# sch_CPU.net
KiCad netlist of a schematic drawn in Altium Designer
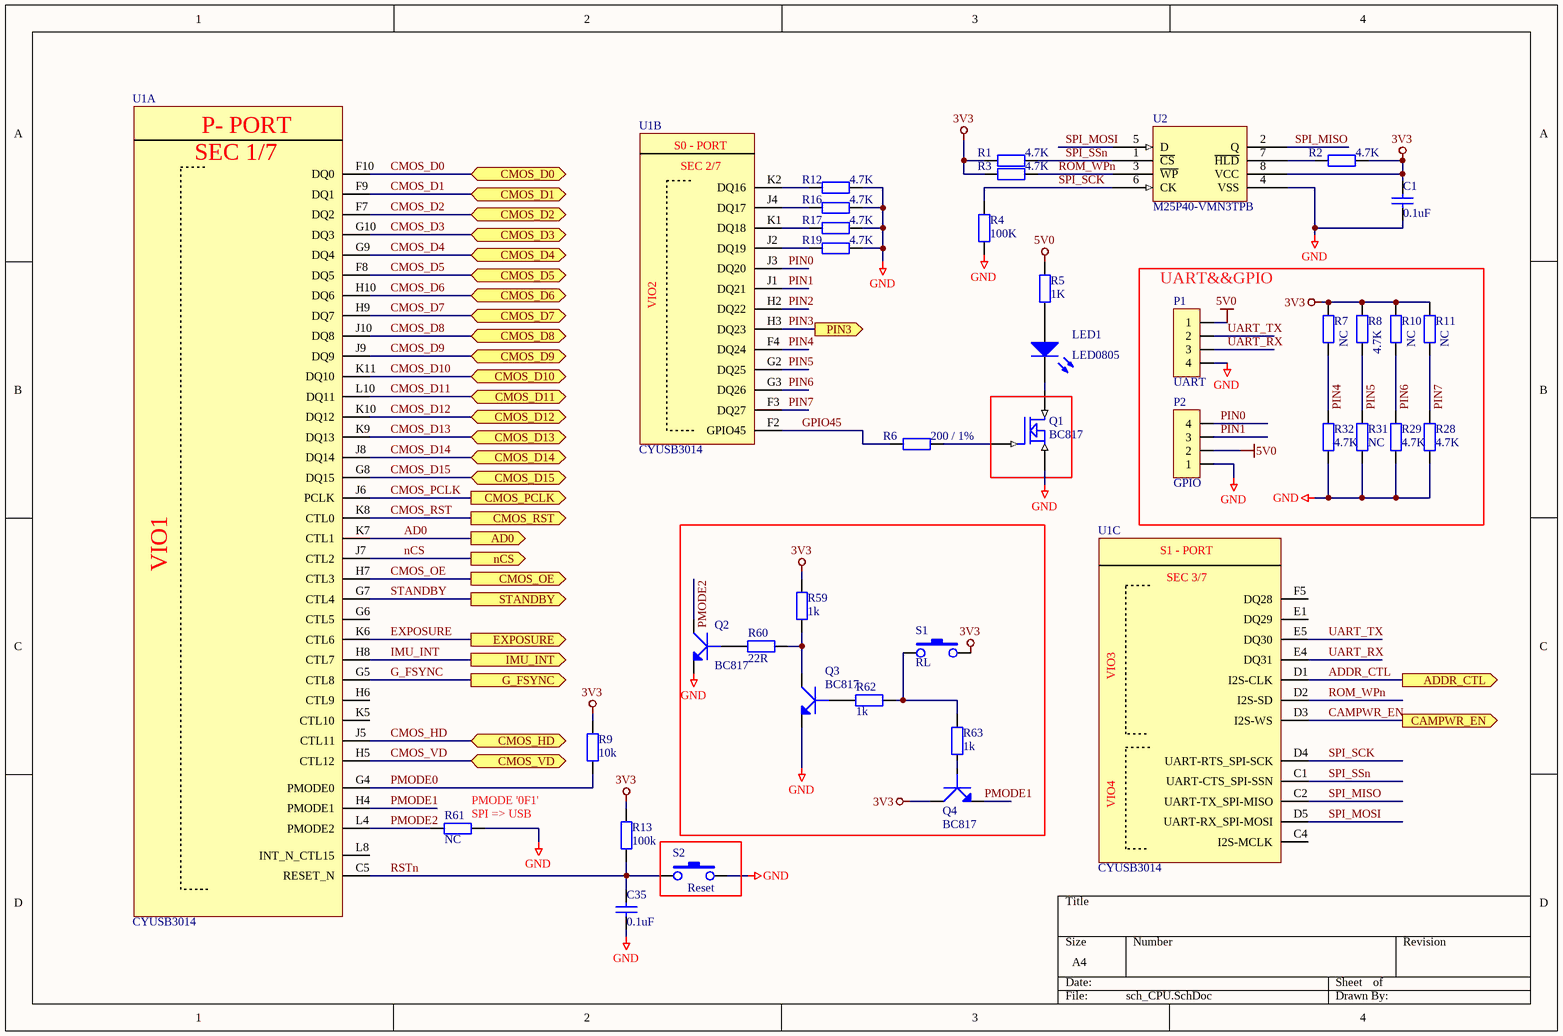
[diagram p0: sch_CPU.SchDoc]

(export (version "E")
  (design (tool "Eeschema 10.0.6"))
  (components
    (comp (ref "C1")
      (value "0.1uF")
      (footprint "0402C")
      (description "Capacitor")
      (fields (field (name "PUBLISHER") "Altium Limited"))
      (libsource (lib "Miscellaneous Devices") (part "Cap"))
    )
    (comp (ref "C35")
      (value "0.1uF")
      (footprint "0402C")
      (description "Capacitor")
      (fields (field (name "PUBLISHER") "Altium Limited"))
      (libsource (lib "Miscellaneous Devices") (part "Cap"))
    )
    (comp (ref "LED1")
      (value "LED0805")
      (footprint "LED0805A_L210W100H60")
      (description "发光二级管")
      (libsource (lib "TXW") (part "LED"))
    )
    (comp (ref "P1")
      (value "UART")
      (footprint "WAFER4_P1.25L6.25W3.4H4.3")
      (libsource (lib "KS_Drive") (part "CON4"))
    )
    (comp (ref "P2")
      (value "GPIO")
      (footprint "WAFER4_P1.25L6.25W3.4H4.3")
      (libsource (lib "") (part "CON4_1"))
    )
    (comp (ref "Q1")
      (value "BC817")
      (footprint "SOT-23L")
      (description "MOSFET N")
      (libsource (lib "TXW") (part "MOSFET N"))
    )
    (comp (ref "Q2")
      (value "BC817")
      (footprint "SOT-23L")
      (description "NPN Transistor")
      (libsource (lib "") (part "NPN_1"))
    )
    (comp (ref "Q3")
      (value "BC817")
      (footprint "SOT-23L")
      (description "NPN Transistor")
      (libsource (lib "") (part "NPN_1"))
    )
    (comp (ref "Q4")
      (value "BC817")
      (footprint "SOT-23L")
      (description "NPN Transistor")
      (libsource (lib "*") (part "NPN"))
    )
    (comp (ref "R1")
      (value "4.7K")
      (footprint "0402R")
      (description "Resistor")
      (fields (field (name "PUBLISHER") "Altium Limited"))
      (libsource (lib "SZG") (part "Resistor"))
    )
    (comp (ref "R2")
      (value "4.7K")
      (footprint "0402R")
      (description "Resistor")
      (fields (field (name "PUBLISHER") "Altium Limited"))
      (libsource (lib "SZG") (part "Resistor"))
    )
    (comp (ref "R3")
      (value "4.7K")
      (footprint "0402R")
      (description "Resistor")
      (fields (field (name "PUBLISHER") "Altium Limited"))
      (libsource (lib "SZG") (part "Resistor"))
    )
    (comp (ref "R4")
      (value "100K")
      (footprint "0402R")
      (description "Resistor")
      (fields (field (name "PUBLISHER") "Altium Limited"))
      (libsource (lib "") (part "Resistor_3"))
    )
    (comp (ref "R5")
      (value "1K")
      (footprint "0402R")
      (description "Resistor")
      (fields (field (name "PUBLISHER") "Altium Limited"))
      (libsource (lib "") (part "Resistor_1"))
    )
    (comp (ref "R6")
      (value "200 / 1%")
      (footprint "0402R")
      (description "Resistor")
      (fields (field (name "Comment") "200R") (field (name "PUBLISHER") "Altium Limited"))
      (libsource (lib "SZG") (part "Resistor"))
    )
    (comp (ref "R7")
      (value "NC")
      (footprint "0402R")
      (description "Resistor")
      (fields (field (name "PUBLISHER") "Altium Limited"))
      (libsource (lib "") (part "Resistor_3"))
    )
    (comp (ref "R8")
      (value "4.7K")
      (footprint "0402R")
      (description "Resistor")
      (fields (field (name "PUBLISHER") "Altium Limited"))
      (libsource (lib "") (part "Resistor_3"))
    )
    (comp (ref "R9")
      (value "10k")
      (footprint "0402R")
      (description "Resistor")
      (fields (field (name "Comment") "10K") (field (name "PUBLISHER") "Altium Limited"))
      (libsource (lib "") (part "Resistor_1"))
    )
    (comp (ref "R10")
      (value "NC")
      (footprint "0402R")
      (description "Resistor")
      (fields (field (name "PUBLISHER") "Altium Limited"))
      (libsource (lib "") (part "Resistor_3"))
    )
    (comp (ref "R11")
      (value "NC")
      (footprint "0402R")
      (description "Resistor")
      (fields (field (name "PUBLISHER") "Altium Limited"))
      (libsource (lib "") (part "Resistor_3"))
    )
    (comp (ref "R12")
      (value "4.7K")
      (footprint "0402R")
      (description "Resistor")
      (fields (field (name "PUBLISHER") "Altium Limited"))
      (libsource (lib "SZG") (part "Resistor"))
    )
    (comp (ref "R13")
      (value "100k")
      (footprint "0402R")
      (description "Resistor")
      (fields (field (name "Comment") "100K") (field (name "PUBLISHER") "Altium Limited"))
      (libsource (lib "") (part "Resistor_1"))
    )
    (comp (ref "R16")
      (value "4.7K")
      (footprint "0402R")
      (description "Resistor")
      (fields (field (name "PUBLISHER") "Altium Limited"))
      (libsource (lib "SZG") (part "Resistor"))
    )
    (comp (ref "R17")
      (value "4.7K")
      (footprint "0402R")
      (description "Resistor")
      (fields (field (name "PUBLISHER") "Altium Limited"))
      (libsource (lib "SZG") (part "Resistor"))
    )
    (comp (ref "R19")
      (value "4.7K")
      (footprint "0402R")
      (description "Resistor")
      (fields (field (name "PUBLISHER") "Altium Limited"))
      (libsource (lib "SZG") (part "Resistor"))
    )
    (comp (ref "R28")
      (value "4.7K")
      (footprint "0402R")
      (description "Resistor")
      (fields (field (name "PUBLISHER") "Altium Limited"))
      (libsource (lib "") (part "Resistor_1"))
    )
    (comp (ref "R29")
      (value "4.7K")
      (footprint "0402R")
      (description "Resistor")
      (fields (field (name "PUBLISHER") "Altium Limited"))
      (libsource (lib "") (part "Resistor_1"))
    )
    (comp (ref "R31")
      (value "NC")
      (footprint "0402R")
      (description "Resistor")
      (fields (field (name "Comment") "N~{C}") (field (name "PUBLISHER") "Altium Limited"))
      (libsource (lib "") (part "Resistor_1"))
    )
    (comp (ref "R32")
      (value "4.7K")
      (footprint "0402R")
      (description "Resistor")
      (fields (field (name "PUBLISHER") "Altium Limited"))
      (libsource (lib "") (part "Resistor_1"))
    )
    (comp (ref "R59")
      (value "1k")
      (footprint "0402R")
      (description "Resistor")
      (fields (field (name "Comment") "1K") (field (name "PUBLISHER") "Altium Limited"))
      (libsource (lib "") (part "Resistor_3"))
    )
    (comp (ref "R60")
      (value "22R")
      (footprint "0402R")
      (description "Resistor")
      (fields (field (name "PUBLISHER") "Altium Limited"))
      (libsource (lib "SZG") (part "Resistor"))
    )
    (comp (ref "R61")
      (value "NC")
      (footprint "0805R")
      (description "Resistor")
      (fields (field (name "PUBLISHER") "Altium Limited"))
      (libsource (lib "") (part "Resistor_2"))
    )
    (comp (ref "R62")
      (value "1k")
      (footprint "0402R")
      (description "Resistor")
      (fields (field (name "PUBLISHER") "Altium Limited"))
      (libsource (lib "") (part "Resistor_2"))
    )
    (comp (ref "R63")
      (value "1k")
      (footprint "0402R")
      (description "Resistor")
      (fields (field (name "PUBLISHER") "Altium Limited"))
      (libsource (lib "") (part "Resistor_1"))
    )
    (comp (ref "S1")
      (value "RL")
      (footprint "SW_L40W30H25_MPTFP")
      (description "Button_sop")
      (libsource (lib "SZG") (part "Button_sop"))
    )
    (comp (ref "S2")
      (value "Reset")
      (footprint "SW_L40W30H25_MPTFP")
      (description "Button_sop")
      (libsource (lib "SZG") (part "Button_sop"))
    )
    (comp (ref "U1")
      (value "CYUSB3014")
      (footprint "FBGA121_P80L100W100H11")
      (libsource (lib "TXW") (part "CYUSB3014"))
    )
    (comp (ref "U2")
      (value "M25P40-VMN3TPB")
      (footprint "SO8N_P127L50W40W62H17")
      (libsource (lib "TXW") (part "M25P40-VMN3TPB"))
    )
  )
  (nets
    (net (code "1") (name "/AD0") (class "Default")
      (node (ref "U1") (pin "K7") (pinfunction "CTL1_K7") (pintype "passive"))
    )
    (net (code "2") (name "/ADDR_CTL") (class "Default")
      (node (ref "U1") (pin "D1") (pinfunction "I2S-CLK_D1") (pintype "passive"))
    )
    (net (code "3") (name "/CAMPWR_EN") (class "Default")
      (node (ref "U1") (pin "D3") (pinfunction "I2S-WS_D3") (pintype "passive"))
    )
    (net (code "4") (name "/CMOS_D0") (class "Default")
      (node (ref "U1") (pin "F10") (pinfunction "DQ0_F10") (pintype "passive"))
    )
    (net (code "5") (name "/CMOS_D1") (class "Default")
      (node (ref "U1") (pin "F9") (pinfunction "DQ1_F9") (pintype "passive"))
    )
    (net (code "6") (name "/CMOS_D2") (class "Default")
      (node (ref "U1") (pin "F7") (pinfunction "DQ2_F7") (pintype "passive"))
    )
    (net (code "7") (name "/CMOS_D3") (class "Default")
      (node (ref "U1") (pin "G10") (pinfunction "DQ3_G10") (pintype "passive"))
    )
    (net (code "8") (name "/CMOS_D4") (class "Default")
      (node (ref "U1") (pin "G9") (pinfunction "DQ4_G9") (pintype "passive"))
    )
    (net (code "9") (name "/CMOS_D5") (class "Default")
      (node (ref "U1") (pin "F8") (pinfunction "DQ5_F8") (pintype "passive"))
    )
    (net (code "10") (name "/CMOS_D6") (class "Default")
      (node (ref "U1") (pin "H10") (pinfunction "DQ6_H10") (pintype "passive"))
    )
    (net (code "11") (name "/CMOS_D7") (class "Default")
      (node (ref "U1") (pin "H9") (pinfunction "DQ7_H9") (pintype "passive"))
    )
    (net (code "12") (name "/CMOS_D8") (class "Default")
      (node (ref "U1") (pin "J10") (pinfunction "DQ8_J10") (pintype "passive"))
    )
    (net (code "13") (name "/CMOS_D9") (class "Default")
      (node (ref "U1") (pin "J9") (pinfunction "DQ9_J9") (pintype "passive"))
    )
    (net (code "14") (name "/CMOS_D10") (class "Default")
      (node (ref "U1") (pin "K11") (pinfunction "DQ10_K11") (pintype "passive"))
    )
    (net (code "15") (name "/CMOS_D11") (class "Default")
      (node (ref "U1") (pin "L10") (pinfunction "DQ11_L10") (pintype "passive"))
    )
    (net (code "16") (name "/CMOS_D12") (class "Default")
      (node (ref "U1") (pin "K10") (pinfunction "DQ12_K10") (pintype "passive"))
    )
    (net (code "17") (name "/CMOS_D13") (class "Default")
      (node (ref "U1") (pin "K9") (pinfunction "DQ13_K9") (pintype "passive"))
    )
    (net (code "18") (name "/CMOS_D14") (class "Default")
      (node (ref "U1") (pin "J8") (pinfunction "DQ14_J8") (pintype "passive"))
    )
    (net (code "19") (name "/CMOS_D15") (class "Default")
      (node (ref "U1") (pin "G8") (pinfunction "DQ15_G8") (pintype "passive"))
    )
    (net (code "20") (name "/CMOS_HD") (class "Default")
      (node (ref "U1") (pin "J5") (pinfunction "CTL11_J5") (pintype "passive"))
    )
    (net (code "21") (name "/CMOS_OE") (class "Default")
      (node (ref "U1") (pin "H7") (pinfunction "CTL3_H7") (pintype "passive"))
    )
    (net (code "22") (name "/CMOS_PCLK") (class "Default")
      (node (ref "U1") (pin "J6") (pinfunction "PCLK_J6") (pintype "passive"))
    )
    (net (code "23") (name "/CMOS_RST") (class "Default")
      (node (ref "U1") (pin "K8") (pinfunction "CTL0_K8") (pintype "passive"))
    )
    (net (code "24") (name "/CMOS_VD") (class "Default")
      (node (ref "U1") (pin "H5") (pinfunction "CTL12_H5") (pintype "passive"))
    )
    (net (code "25") (name "/EXPOSURE") (class "Default")
      (node (ref "U1") (pin "K6") (pinfunction "CTL6_K6") (pintype "passive"))
    )
    (net (code "26") (name "/GPIO45") (class "Default")
      (node (ref "R6") (pin "1") (pinfunction "1_1") (pintype "passive"))
      (node (ref "U1") (pin "F2") (pinfunction "GPIO45_F2") (pintype "passive"))
    )
    (net (code "27") (name "/G_FSYNC") (class "Default")
      (node (ref "U1") (pin "G5") (pinfunction "CTL8_G5") (pintype "passive"))
    )
    (net (code "28") (name "/IMU_INT") (class "Default")
      (node (ref "U1") (pin "H8") (pinfunction "CTL7_H8") (pintype "passive"))
    )
    (net (code "29") (name "/PIN0") (class "Default")
      (node (ref "P2") (pin "4") (pinfunction "4_4") (pintype "passive"))
      (node (ref "U1") (pin "J3") (pinfunction "DQ20_J3") (pintype "passive"))
    )
    (net (code "30") (name "/PIN1") (class "Default")
      (node (ref "P2") (pin "3") (pinfunction "3_3") (pintype "passive"))
      (node (ref "U1") (pin "J1") (pinfunction "DQ21_J1") (pintype "passive"))
    )
    (net (code "31") (name "/PIN2") (class "Default")
      (node (ref "U1") (pin "H2") (pinfunction "DQ22_H2") (pintype "passive"))
    )
    (net (code "32") (name "/PIN3") (class "Default")
      (node (ref "U1") (pin "H3") (pinfunction "DQ23_H3") (pintype "passive"))
    )
    (net (code "33") (name "/PIN4") (class "Default")
      (node (ref "R32") (pin "1") (pinfunction "1_1") (pintype "passive"))
      (node (ref "R7") (pin "1") (pinfunction "1_1") (pintype "passive"))
      (node (ref "U1") (pin "F4") (pinfunction "DQ24_F4") (pintype "passive"))
    )
    (net (code "34") (name "/PIN5") (class "Default")
      (node (ref "R31") (pin "1") (pinfunction "1_1") (pintype "passive"))
      (node (ref "R8") (pin "1") (pinfunction "1_1") (pintype "passive"))
      (node (ref "U1") (pin "G2") (pinfunction "DQ25_G2") (pintype "passive"))
    )
    (net (code "35") (name "/PIN6") (class "Default")
      (node (ref "R10") (pin "1") (pinfunction "1_1") (pintype "passive"))
      (node (ref "R29") (pin "1") (pinfunction "1_1") (pintype "passive"))
      (node (ref "U1") (pin "G3") (pinfunction "DQ26_G3") (pintype "passive"))
    )
    (net (code "36") (name "/PIN7") (class "Default")
      (node (ref "R11") (pin "1") (pinfunction "1_1") (pintype "passive"))
      (node (ref "R28") (pin "1") (pinfunction "1_1") (pintype "passive"))
      (node (ref "U1") (pin "F3") (pinfunction "DQ27_F3") (pintype "passive"))
    )
    (net (code "37") (name "/PMODE0") (class "Default")
      (node (ref "R9") (pin "2") (pinfunction "2_2") (pintype "passive"))
      (node (ref "U1") (pin "G4") (pinfunction "PMODE0_G4") (pintype "passive"))
    )
    (net (code "38") (name "/PMODE1") (class "Default")
      (node (ref "Q4") (pin "2") (pinfunction "E_2") (pintype "passive"))
      (node (ref "U1") (pin "H4") (pinfunction "PMODE1_H4") (pintype "passive"))
    )
    (net (code "39") (name "/PMODE2") (class "Default")
      (node (ref "Q2") (pin "3") (pinfunction "C_3") (pintype "passive"))
      (node (ref "R61") (pin "2") (pinfunction "2_2") (pintype "passive"))
      (node (ref "U1") (pin "L4") (pinfunction "PMODE2_L4") (pintype "passive"))
    )
    (net (code "40") (name "/ROM_WPn") (class "Default")
      (node (ref "R3") (pin "2") (pinfunction "2_2") (pintype "passive"))
      (node (ref "U1") (pin "D2") (pinfunction "I2S-SD_D2") (pintype "passive"))
      (node (ref "U2") (pin "3") (pinfunction "~{WP}_3") (pintype "passive"))
    )
    (net (code "41") (name "/RSTn") (class "Default")
      (node (ref "C35") (pin "2") (pinfunction "2_2") (pintype "passive"))
      (node (ref "R13") (pin "2") (pinfunction "2_2") (pintype "passive"))
      (node (ref "S2") (pin "1") (pinfunction "1_1") (pintype "passive"))
      (node (ref "U1") (pin "C5") (pinfunction "RESET_N_C5") (pintype "passive"))
    )
    (net (code "42") (name "/SPI_MISO") (class "Default")
      (node (ref "U1") (pin "C2") (pinfunction "UART-TX_SPI-MISO_C2") (pintype "passive"))
      (node (ref "U2") (pin "2") (pinfunction "Q_2") (pintype "passive"))
    )
    (net (code "43") (name "/SPI_MOSI") (class "Default")
      (node (ref "U1") (pin "D5") (pinfunction "UART-RX_SPI-MOSI_D5") (pintype "passive"))
      (node (ref "U2") (pin "5") (pinfunction "D_5") (pintype "input"))
    )
    (net (code "44") (name "/SPI_SCK") (class "Default")
      (node (ref "R4") (pin "2") (pinfunction "2_2") (pintype "passive"))
      (node (ref "U1") (pin "D4") (pinfunction "UART-RTS_SPI-SCK_D4") (pintype "passive"))
      (node (ref "U2") (pin "6") (pinfunction "CK_6") (pintype "input"))
    )
    (net (code "45") (name "/SPI_SSn") (class "Default")
      (node (ref "R1") (pin "2") (pinfunction "2_2") (pintype "passive"))
      (node (ref "U1") (pin "C1") (pinfunction "UART-CTS_SPI-SSN_C1") (pintype "passive"))
      (node (ref "U2") (pin "1") (pinfunction "~{CS}_1") (pintype "passive"))
    )
    (net (code "46") (name "/STANDBY") (class "Default")
      (node (ref "U1") (pin "G7") (pinfunction "CTL4_G7") (pintype "passive"))
    )
    (net (code "47") (name "/UART_RX") (class "Default")
      (node (ref "P1") (pin "3") (pinfunction "3_3") (pintype "passive"))
      (node (ref "U1") (pin "E4") (pinfunction "DQ31_E4") (pintype "passive"))
    )
    (net (code "48") (name "/UART_TX") (class "Default")
      (node (ref "P1") (pin "2") (pinfunction "2_2") (pintype "passive"))
      (node (ref "U1") (pin "E5") (pinfunction "DQ30_E5") (pintype "passive"))
    )
    (net (code "49") (name "/nCS") (class "Default")
      (node (ref "U1") (pin "J7") (pinfunction "CTL2_J7") (pintype "passive"))
    )
    (net (code "50") (name "3V3") (class "Default")
      (node (ref "C1") (pin "2") (pinfunction "2_2") (pintype "passive"))
      (node (ref "Q4") (pin "3") (pinfunction "C_3") (pintype "passive"))
      (node (ref "R1") (pin "1") (pinfunction "1_1") (pintype "passive"))
      (node (ref "R10") (pin "2") (pinfunction "2_2") (pintype "passive"))
      (node (ref "R11") (pin "2") (pinfunction "2_2") (pintype "passive"))
      (node (ref "R13") (pin "1") (pinfunction "1_1") (pintype "passive"))
      (node (ref "R2") (pin "2") (pinfunction "2_2") (pintype "passive"))
      (node (ref "R3") (pin "1") (pinfunction "1_1") (pintype "passive"))
      (node (ref "R59") (pin "2") (pinfunction "2_2") (pintype "passive"))
      (node (ref "R7") (pin "2") (pinfunction "2_2") (pintype "passive"))
      (node (ref "R8") (pin "2") (pinfunction "2_2") (pintype "passive"))
      (node (ref "R9") (pin "1") (pinfunction "1_1") (pintype "passive"))
      (node (ref "S1") (pin "1") (pinfunction "1_1") (pintype "passive"))
      (node (ref "U2") (pin "8") (pinfunction "VCC_8") (pintype "passive"))
    )
    (net (code "51") (name "5V0") (class "Default")
      (node (ref "P1") (pin "1") (pinfunction "1_1") (pintype "passive"))
      (node (ref "P2") (pin "2") (pinfunction "2_2") (pintype "passive"))
      (node (ref "R5") (pin "1") (pinfunction "1_1") (pintype "passive"))
    )
    (net (code "52") (name "GND") (class "Default")
      (node (ref "C1") (pin "1") (pinfunction "1_1") (pintype "passive"))
      (node (ref "C35") (pin "1") (pinfunction "1_1") (pintype "passive"))
      (node (ref "P1") (pin "4") (pinfunction "4_4") (pintype "passive"))
      (node (ref "P2") (pin "1") (pinfunction "1_1") (pintype "passive"))
      (node (ref "Q1") (pin "2") (pinfunction "S_2") (pintype "input"))
      (node (ref "Q2") (pin "2") (pinfunction "E_2") (pintype "passive"))
      (node (ref "Q3") (pin "2") (pinfunction "E_2") (pintype "passive"))
      (node (ref "R12") (pin "2") (pinfunction "2_2") (pintype "passive"))
      (node (ref "R16") (pin "2") (pinfunction "2_2") (pintype "passive"))
      (node (ref "R17") (pin "2") (pinfunction "2_2") (pintype "passive"))
      (node (ref "R19") (pin "2") (pinfunction "2_2") (pintype "passive"))
      (node (ref "R28") (pin "2") (pinfunction "2_2") (pintype "passive"))
      (node (ref "R29") (pin "2") (pinfunction "2_2") (pintype "passive"))
      (node (ref "R31") (pin "2") (pinfunction "2_2") (pintype "passive"))
      (node (ref "R32") (pin "2") (pinfunction "2_2") (pintype "passive"))
      (node (ref "R4") (pin "1") (pinfunction "1_1") (pintype "passive"))
      (node (ref "R61") (pin "1") (pinfunction "1_1") (pintype "passive"))
      (node (ref "S2") (pin "2") (pinfunction "2_2") (pintype "passive"))
      (node (ref "U2") (pin "4") (pinfunction "VSS_4") (pintype "passive"))
    )
    (net (code "53") (name "Net-(LED1-A)") (class "Default")
      (node (ref "LED1") (pin "1") (pinfunction "A_1") (pintype "passive"))
      (node (ref "R5") (pin "2") (pinfunction "2_2") (pintype "passive"))
    )
    (net (code "54") (name "Net-(LED1-K)") (class "Default")
      (node (ref "LED1") (pin "2") (pinfunction "K_2") (pintype "passive"))
      (node (ref "Q1") (pin "3") (pinfunction "D_3") (pintype "input"))
    )
    (net (code "55") (name "Net-(Q1-G)") (class "Default")
      (node (ref "Q1") (pin "1") (pinfunction "G_1") (pintype "input"))
      (node (ref "R6") (pin "2") (pinfunction "2_2") (pintype "passive"))
    )
    (net (code "56") (name "Net-(Q2-B)") (class "Default")
      (node (ref "Q2") (pin "1") (pinfunction "B_1") (pintype "passive"))
      (node (ref "R60") (pin "1") (pinfunction "1_1") (pintype "passive"))
    )
    (net (code "57") (name "Net-(Q3-B)") (class "Default")
      (node (ref "Q3") (pin "1") (pinfunction "B_1") (pintype "passive"))
      (node (ref "R62") (pin "2") (pinfunction "2_2") (pintype "passive"))
    )
    (net (code "58") (name "Net-(Q3-C)") (class "Default")
      (node (ref "Q3") (pin "3") (pinfunction "C_3") (pintype "passive"))
      (node (ref "R59") (pin "1") (pinfunction "1_1") (pintype "passive"))
      (node (ref "R60") (pin "2") (pinfunction "2_2") (pintype "passive"))
    )
    (net (code "59") (name "Net-(Q4-B)") (class "Default")
      (node (ref "Q4") (pin "1") (pinfunction "B_1") (pintype "passive"))
      (node (ref "R63") (pin "2") (pinfunction "2_2") (pintype "passive"))
    )
    (net (code "60") (name "Net-(R62-Pad1)") (class "Default")
      (node (ref "R62") (pin "1") (pinfunction "1_1") (pintype "passive"))
      (node (ref "R63") (pin "1") (pinfunction "1_1") (pintype "passive"))
      (node (ref "S1") (pin "2") (pinfunction "2_2") (pintype "passive"))
    )
    (net (code "61") (name "Net-(U1B-DQ16)") (class "Default")
      (node (ref "R12") (pin "1") (pinfunction "1_1") (pintype "passive"))
      (node (ref "U1") (pin "K2") (pinfunction "DQ16_K2") (pintype "passive"))
    )
    (net (code "62") (name "Net-(U1B-DQ17)") (class "Default")
      (node (ref "R16") (pin "1") (pinfunction "1_1") (pintype "passive"))
      (node (ref "U1") (pin "J4") (pinfunction "DQ17_J4") (pintype "passive"))
    )
    (net (code "63") (name "Net-(U1B-DQ18)") (class "Default")
      (node (ref "R17") (pin "1") (pinfunction "1_1") (pintype "passive"))
      (node (ref "U1") (pin "K1") (pinfunction "DQ18_K1") (pintype "passive"))
    )
    (net (code "64") (name "Net-(U1B-DQ19)") (class "Default")
      (node (ref "R19") (pin "1") (pinfunction "1_1") (pintype "passive"))
      (node (ref "U1") (pin "J2") (pinfunction "DQ19_J2") (pintype "passive"))
    )
    (net (code "65") (name "Net-(U2-~{HLD})") (class "Default")
      (node (ref "R2") (pin "1") (pinfunction "1_1") (pintype "passive"))
      (node (ref "U2") (pin "7") (pinfunction "~{HLD}_7") (pintype "passive"))
    )
    (net (code "66") (name "unconnected-(U1A-CTL5-PadG6)") (class "Default")
      (node (ref "U1") (pin "G6") (pinfunction "CTL5_G6") (pintype "passive"))
    )
    (net (code "67") (name "unconnected-(U1A-CTL9-PadH6)") (class "Default")
      (node (ref "U1") (pin "H6") (pinfunction "CTL9_H6") (pintype "passive"))
    )
    (net (code "68") (name "unconnected-(U1A-CTL10-PadK5)") (class "Default")
      (node (ref "U1") (pin "K5") (pinfunction "CTL10_K5") (pintype "passive"))
    )
    (net (code "69") (name "unconnected-(U1A-INT_N_CTL15-PadL8)") (class "Default")
      (node (ref "U1") (pin "L8") (pinfunction "INT_N_CTL15_L8") (pintype "passive"))
    )
    (net (code "70") (name "unconnected-(U1C-DQ28-PadF5)") (class "Default")
      (node (ref "U1") (pin "F5") (pinfunction "DQ28_F5") (pintype "passive"))
    )
    (net (code "71") (name "unconnected-(U1C-DQ29-PadE1)") (class "Default")
      (node (ref "U1") (pin "E1") (pinfunction "DQ29_E1") (pintype "passive"))
    )
    (net (code "72") (name "unconnected-(U1C-I2S-MCLK-PadC4)") (class "Default")
      (node (ref "U1") (pin "C4") (pinfunction "I2S-MCLK_C4") (pintype "passive"))
    )
  )
)
